# Master_HV_PCB.net
KiCad netlist of a schematic drawn in Altium Designer
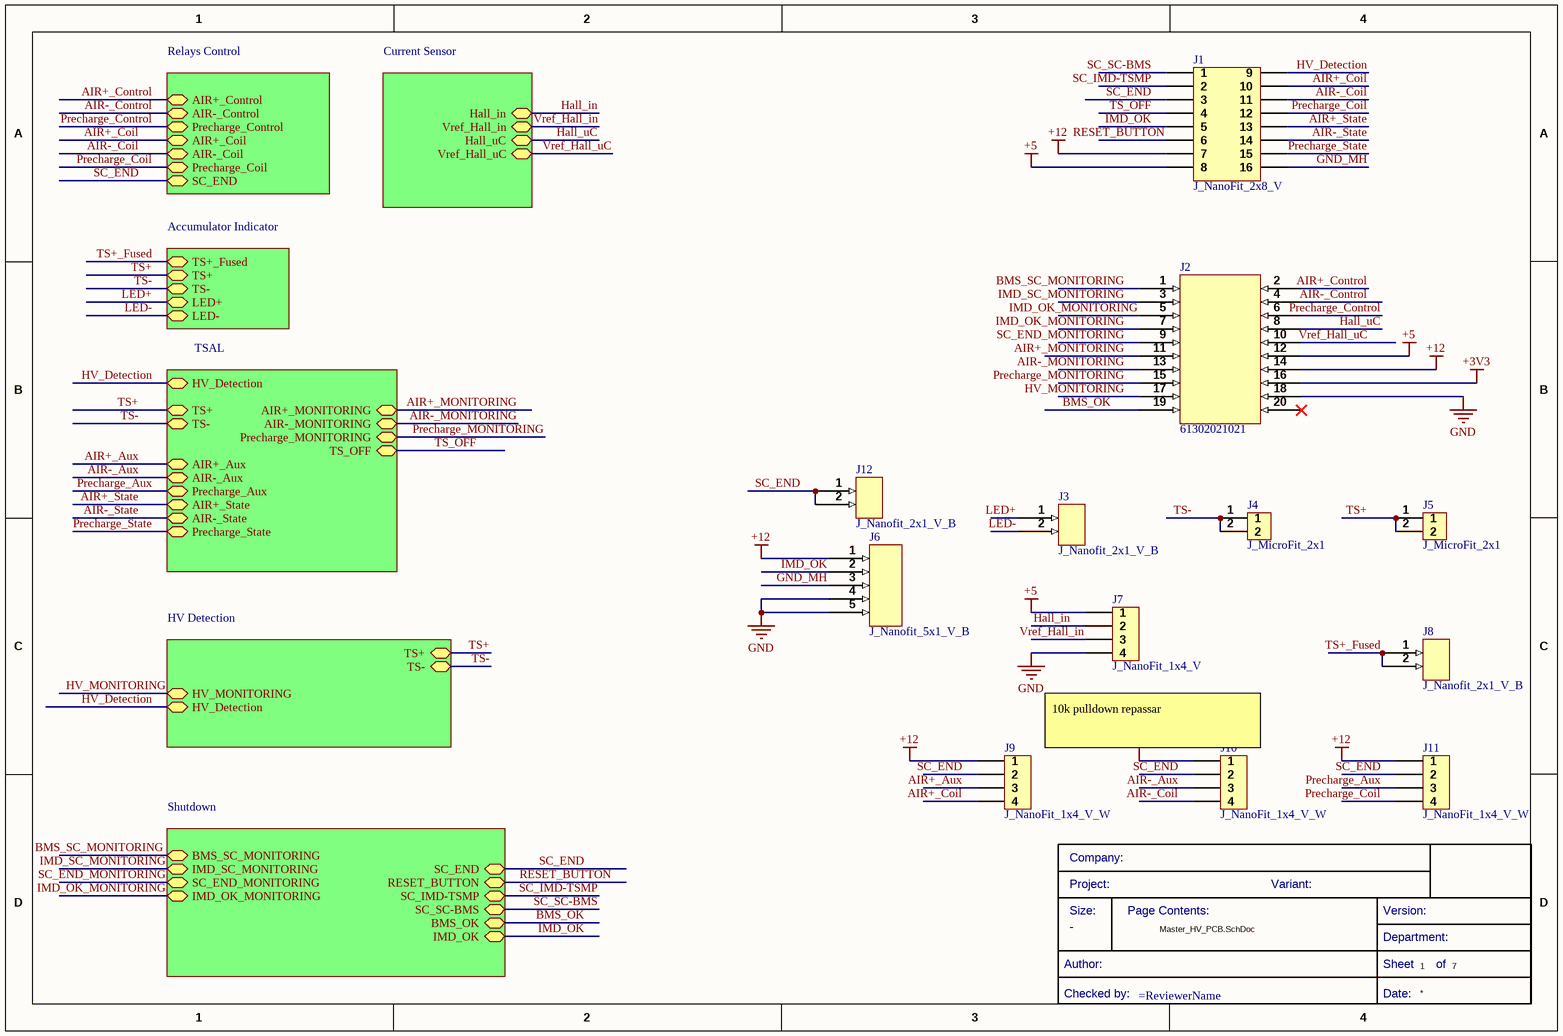
[diagram p0: Master_HV_PCB.SchDoc]

(export (version "E")
  (design (tool "Eeschema 10.0.6"))
  (components
    (comp (ref "J1")
      (value "J_NanoFit_2x8_V")
      (footprint "J_NanoFit_2x8_V")
      (fields (field (name ".CREATOR") "AC"))
      (libsource (lib "EMEA- E-Tech Racing- I'Escola d'Enginyeria de Barcelona Est") (part "J_NanoFit_2x8_V"))
    )
    (comp (ref "J2")
      (value "61302021021")
      (footprint "61302021021")
      (libsource (lib "EMEA- E-Tech Racing- I'Escola d'Enginyeria de Barcelona Est") (part "61302021021-Symbol-1"))
    )
    (comp (ref "J3")
      (value "J_Nanofit_2x1_V_B")
      (footprint "FP-105309-1102-MFG")
      (description "Conn HDR 2 POS 2.5mm Solder ST Thru-Hole 2 Terminal 1 Port Nano-Fit Tray")
      (libsource (lib "EMEA- E-Tech Racing- I'Escola d'Enginyeria de Barcelona Est") (part "J_Nanofit_2x1_V_B"))
    )
    (comp (ref "J4")
      (value "J_MicroFit_2x1")
      (footprint "J_MicroFit_2x1")
      (description "Header 1 Row Vertical Polarizing Peg 2 Pin SMT/Glow Wire Compatible Tin Plate")
      (libsource (lib "EMEA- E-Tech Racing- I'Escola d'Enginyeria de Barcelona Est") (part "J_MicroFit_2x1"))
    )
    (comp (ref "J5")
      (value "J_MicroFit_2x1")
      (footprint "J_MicroFit_2x1")
      (description "Header 1 Row Vertical Polarizing Peg 2 Pin SMT/Glow Wire Compatible Tin Plate")
      (libsource (lib "EMEA- E-Tech Racing- I'Escola d'Enginyeria de Barcelona Est") (part "J_MicroFit_2x1"))
    )
    (comp (ref "J6")
      (value "J_Nanofit_5x1_V_B")
      (footprint "105309-1205-Footprint-1")
      (description "Nano-Fit Vertical Header Through Hole 2.50mm Pitch Single Row 5 Circuits with Kinked Pins 0.38")
      (libsource (lib "EMEA- E-Tech Racing- I'Escola d'Enginyeria de Barcelona Est") (part "J_Nanofit_5x1V_V_B"))
    )
    (comp (ref "J7")
      (value "J_NanoFit_1x4_V")
      (footprint "J_NanoFit_1x4_V")
      (description "Nano-Fit Vertical Header Through Hole 2.50mm Pitch Single Row 4 Circuits with Kinked Pins 0.38")
      (fields (field (name ".CREATOR") "DO"))
      (libsource (lib "EMEA- E-Tech Racing- I'Escola d'Enginyeria de Barcelona Est") (part "J_NanoFit_1x4_V_W"))
    )
    (comp (ref "J8")
      (value "J_Nanofit_2x1_V_B")
      (footprint "FP-105309-1102-MFG")
      (description "Conn HDR 2 POS 2.5mm Solder ST Thru-Hole 2 Terminal 1 Port Nano-Fit Tray")
      (libsource (lib "EMEA- E-Tech Racing- I'Escola d'Enginyeria de Barcelona Est") (part "J_Nanofit_2x1_V_B"))
    )
    (comp (ref "J9")
      (value "J_NanoFit_1x4_V_W")
      (footprint "J_NanoFit_1x4_V")
      (description "Conn HDR 4 POS 2.5mm Solder ST Thru-Hole 4 Terminal 1 Port Nano-Fit Tray")
      (fields (field (name ".CREATOR") "DR"))
      (libsource (lib "EMEA- E-Tech Racing- I'Escola d'Enginyeria de Barcelona Est") (part "J_NanoFit_1x4_V_W"))
    )
    (comp (ref "J10")
      (value "J_NanoFit_1x4_V_W")
      (footprint "J_NanoFit_1x4_V")
      (description "Conn HDR 4 POS 2.5mm Solder ST Thru-Hole 4 Terminal 1 Port Nano-Fit Tray")
      (fields (field (name ".CREATOR") "DR"))
      (libsource (lib "EMEA- E-Tech Racing- I'Escola d'Enginyeria de Barcelona Est") (part "J_NanoFit_1x4_V_W"))
    )
    (comp (ref "J11")
      (value "J_NanoFit_1x4_V_W")
      (footprint "J_NanoFit_1x4_V")
      (description "Conn HDR 4 POS 2.5mm Solder ST Thru-Hole 4 Terminal 1 Port Nano-Fit Tray")
      (fields (field (name ".CREATOR") "DR"))
      (libsource (lib "EMEA- E-Tech Racing- I'Escola d'Enginyeria de Barcelona Est") (part "J_NanoFit_1x4_V_W"))
    )
    (comp (ref "J12")
      (value "J_Nanofit_2x1_V_B")
      (footprint "FP-105309-1102-MFG")
      (description "Conn HDR 2 POS 2.5mm Solder ST Thru-Hole 2 Terminal 1 Port Nano-Fit Tray")
      (libsource (lib "EMEA- E-Tech Racing- I'Escola d'Enginyeria de Barcelona Est") (part "J_Nanofit_2x1_V_B"))
    )
  )
  (nets
    (net (code "1") (name "+3V3") (class "Default")
      (node (ref "J2") (pin "16") (pinfunction "16_16") (pintype "input"))
    )
    (net (code "2") (name "+5") (class "Default")
      (node (ref "J1") (pin "8") (pinfunction "8_8") (pintype "passive"))
      (node (ref "J2") (pin "12") (pinfunction "12_12") (pintype "input"))
      (node (ref "J7") (pin "1") (pinfunction "1_1") (pintype "passive"))
    )
    (net (code "3") (name "+12") (class "Default")
      (node (ref "J1") (pin "7") (pinfunction "7_7") (pintype "passive"))
      (node (ref "J10") (pin "1") (pinfunction "1_1") (pintype "passive"))
      (node (ref "J11") (pin "1") (pinfunction "1_1") (pintype "passive"))
      (node (ref "J2") (pin "14") (pinfunction "14_14") (pintype "input"))
      (node (ref "J6") (pin "1") (pinfunction "1_1") (pintype "input"))
      (node (ref "J9") (pin "1") (pinfunction "1_1") (pintype "passive"))
    )
    (net (code "5") (name "/AIR+_Aux") (class "Default")
      (node (ref "J9") (pin "3") (pinfunction "3_3") (pintype "passive"))
    )
    (net (code "6") (name "/AIR+_Coil") (class "Default")
      (node (ref "J1") (pin "10") (pinfunction "10_10") (pintype "passive"))
      (node (ref "J9") (pin "4") (pinfunction "4_4") (pintype "passive"))
    )
    (net (code "7") (name "/AIR+_Control") (class "Default")
      (node (ref "J2") (pin "2") (pinfunction "2_2") (pintype "input"))
    )
    (net (code "8") (name "/AIR+_MONITORING") (class "Default")
      (node (ref "J2") (pin "11") (pinfunction "11_11") (pintype "input"))
    )
    (net (code "9") (name "/AIR+_State") (class "Default")
      (node (ref "J1") (pin "13") (pinfunction "13_13") (pintype "passive"))
    )
    (net (code "10") (name "/AIR-_Aux") (class "Default")
      (node (ref "J10") (pin "3") (pinfunction "3_3") (pintype "passive"))
    )
    (net (code "11") (name "/AIR-_Coil") (class "Default")
      (node (ref "J1") (pin "11") (pinfunction "11_11") (pintype "passive"))
      (node (ref "J10") (pin "4") (pinfunction "4_4") (pintype "passive"))
    )
    (net (code "12") (name "/AIR-_Control") (class "Default")
      (node (ref "J2") (pin "4") (pinfunction "4_4") (pintype "input"))
    )
    (net (code "13") (name "/AIR-_MONITORING") (class "Default")
      (node (ref "J2") (pin "13") (pinfunction "13_13") (pintype "input"))
    )
    (net (code "14") (name "/AIR-_State") (class "Default")
      (node (ref "J1") (pin "14") (pinfunction "14_14") (pintype "passive"))
    )
    (net (code "15") (name "/BMS_OK") (class "Default")
      (node (ref "J2") (pin "19") (pinfunction "19_19") (pintype "input"))
    )
    (net (code "16") (name "/BMS_SC_MONITORING") (class "Default")
      (node (ref "J2") (pin "1") (pinfunction "1_1") (pintype "input"))
    )
    (net (code "17") (name "/GND_MH") (class "Default")
      (node (ref "J1") (pin "16") (pinfunction "16_16") (pintype "passive"))
      (node (ref "J6") (pin "3") (pinfunction "3_3") (pintype "input"))
    )
    (net (code "18") (name "/HV_Detection") (class "Default")
      (node (ref "J1") (pin "9") (pinfunction "9_9") (pintype "passive"))
    )
    (net (code "19") (name "/HV_MONITORING") (class "Default")
      (node (ref "J2") (pin "17") (pinfunction "17_17") (pintype "input"))
    )
    (net (code "20") (name "/Hall_in") (class "Default")
      (node (ref "J7") (pin "2") (pinfunction "2_2") (pintype "passive"))
    )
    (net (code "21") (name "/Hall_uC") (class "Default")
      (node (ref "J2") (pin "8") (pinfunction "8_8") (pintype "input"))
    )
    (net (code "22") (name "/IMD_OK") (class "Default")
      (node (ref "J1") (pin "5") (pinfunction "5_5") (pintype "passive"))
      (node (ref "J6") (pin "2") (pinfunction "2_2") (pintype "input"))
    )
    (net (code "23") (name "/IMD_OK_MONITORING") (class "Default")
      (node (ref "J2") (pin "5") (pinfunction "5_5") (pintype "input"))
      (node (ref "J2") (pin "7") (pinfunction "7_7") (pintype "input"))
    )
    (net (code "24") (name "/IMD_SC_MONITORING") (class "Default")
      (node (ref "J2") (pin "3") (pinfunction "3_3") (pintype "input"))
    )
    (net (code "25") (name "/LED+") (class "Default")
      (node (ref "J3") (pin "1") (pinfunction "1_1") (pintype "input"))
    )
    (net (code "26") (name "/LED-") (class "Default")
      (node (ref "J3") (pin "2") (pinfunction "2_2") (pintype "input"))
    )
    (net (code "27") (name "/Precharge_Aux") (class "Default")
      (node (ref "J11") (pin "3") (pinfunction "3_3") (pintype "passive"))
    )
    (net (code "28") (name "/Precharge_Coil") (class "Default")
      (node (ref "J1") (pin "12") (pinfunction "12_12") (pintype "passive"))
      (node (ref "J11") (pin "4") (pinfunction "4_4") (pintype "passive"))
    )
    (net (code "29") (name "/Precharge_Control") (class "Default")
      (node (ref "J2") (pin "6") (pinfunction "6_6") (pintype "input"))
    )
    (net (code "30") (name "/Precharge_MONITORING") (class "Default")
      (node (ref "J2") (pin "15") (pinfunction "15_15") (pintype "input"))
    )
    (net (code "31") (name "/Precharge_State") (class "Default")
      (node (ref "J1") (pin "15") (pinfunction "15_15") (pintype "passive"))
    )
    (net (code "32") (name "/RESET_BUTTON") (class "Default")
      (node (ref "J1") (pin "6") (pinfunction "6_6") (pintype "passive"))
    )
    (net (code "33") (name "/SC_END") (class "Default")
      (node (ref "J1") (pin "3") (pinfunction "3_3") (pintype "passive"))
      (node (ref "J10") (pin "2") (pinfunction "2_2") (pintype "passive"))
      (node (ref "J11") (pin "2") (pinfunction "2_2") (pintype "passive"))
      (node (ref "J12") (pin "1") (pinfunction "1_1") (pintype "input"))
      (node (ref "J12") (pin "2") (pinfunction "2_2") (pintype "input"))
      (node (ref "J9") (pin "2") (pinfunction "2_2") (pintype "passive"))
    )
    (net (code "34") (name "/SC_END_MONITORING") (class "Default")
      (node (ref "J2") (pin "9") (pinfunction "9_9") (pintype "input"))
    )
    (net (code "35") (name "/SC_IMD-TSMP") (class "Default")
      (node (ref "J1") (pin "2") (pinfunction "2_2") (pintype "passive"))
    )
    (net (code "36") (name "/SC_SC-BMS") (class "Default")
      (node (ref "J1") (pin "1") (pinfunction "1_1") (pintype "passive"))
    )
    (net (code "37") (name "/TS+") (class "Default")
      (node (ref "J5") (pin "1") (pinfunction "1_1") (pintype "passive"))
      (node (ref "J5") (pin "2") (pinfunction "2_2") (pintype "passive"))
    )
    (net (code "38") (name "/TS+_Fused") (class "Default")
      (node (ref "J8") (pin "1") (pinfunction "1_1") (pintype "input"))
      (node (ref "J8") (pin "2") (pinfunction "2_2") (pintype "input"))
    )
    (net (code "39") (name "/TS-") (class "Default")
      (node (ref "J4") (pin "1") (pinfunction "1_1") (pintype "passive"))
      (node (ref "J4") (pin "2") (pinfunction "2_2") (pintype "passive"))
    )
    (net (code "40") (name "/TS_OFF") (class "Default")
      (node (ref "J1") (pin "4") (pinfunction "4_4") (pintype "passive"))
    )
    (net (code "41") (name "/Vref_Hall_in") (class "Default")
      (node (ref "J7") (pin "3") (pinfunction "3_3") (pintype "passive"))
    )
    (net (code "42") (name "/Vref_Hall_uC") (class "Default")
      (node (ref "J2") (pin "10") (pinfunction "10_10") (pintype "input"))
    )
    (net (code "43") (name "GND") (class "Default")
      (node (ref "J2") (pin "18") (pinfunction "18_18") (pintype "input"))
      (node (ref "J6") (pin "4") (pinfunction "4_4") (pintype "input"))
      (node (ref "J6") (pin "5") (pinfunction "5_5") (pintype "input"))
      (node (ref "J7") (pin "4") (pinfunction "4_4") (pintype "passive"))
    )
    (net (code "44") (name "unconnected-(J2-Pad20)") (class "Default")
      (node (ref "J2") (pin "20") (pinfunction "20_20") (pintype "input+no_connect"))
    )
  )
)
